# msp430g2230_breakout.net
KiCad netlist of a schematic drawn in EAGLE
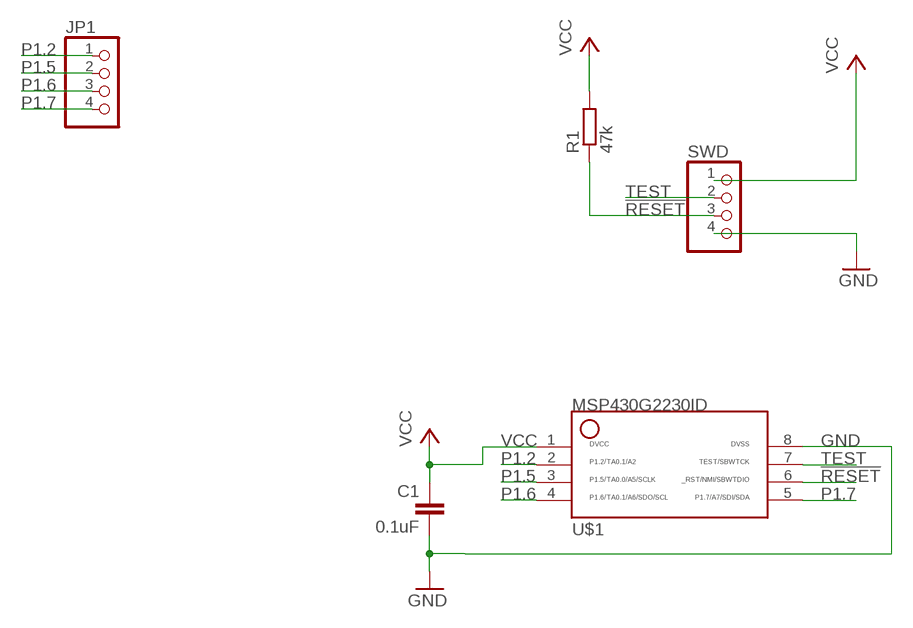
[diagram p0: schematic, sheet 1]

(export (version "E")
  (design (tool "Eeschema 10.0.6"))
  (components
    (comp (ref "C1")
      (value "0.1uF")
      (footprint "eagle-import:C0805")
      (libsource (lib "eagle-import") (part "C-EUC0805"))
    )
    (comp (ref "JP1")
      (value "PINHD-1X4")
      (footprint "eagle-import:1X04")
      (libsource (lib "eagle-import") (part "PINHD-1X4"))
    )
    (comp (ref "R1")
      (value "47k")
      (footprint "eagle-import:R0805")
      (libsource (lib "eagle-import") (part "R-EU_R0805"))
    )
    (comp (ref "SWD")
      (value "PINHD-1X4")
      (footprint "eagle-import:1X04")
      (libsource (lib "eagle-import") (part "PINHD-1X4"))
    )
    (comp (ref "U$1")
      (value "MSP430G2230ID")
      (footprint "eagle-import:SO08")
      (libsource (lib "eagle-import") (part "MSP430G2230ID"))
    )
  )
  (nets
    (net (code "1") (name "/P1.2") (class "Default")
      (node (ref "JP1") (pin "1") (pinfunction "1_1") (pintype "passive"))
      (node (ref "U$1") (pin "2") (pinfunction "2_2") (pintype "bidirectional"))
    )
    (net (code "2") (name "/P1.5") (class "Default")
      (node (ref "JP1") (pin "2") (pinfunction "2_2") (pintype "passive"))
      (node (ref "U$1") (pin "3") (pinfunction "3_3") (pintype "bidirectional"))
    )
    (net (code "3") (name "/P1.6") (class "Default")
      (node (ref "JP1") (pin "3") (pinfunction "3_3") (pintype "passive"))
      (node (ref "U$1") (pin "4") (pinfunction "4_4") (pintype "bidirectional"))
    )
    (net (code "4") (name "/P1.7") (class "Default")
      (node (ref "JP1") (pin "4") (pinfunction "4_4") (pintype "passive"))
      (node (ref "U$1") (pin "5") (pinfunction "5_5") (pintype "bidirectional"))
    )
    (net (code "5") (name "/TEST") (class "Default")
      (node (ref "SWD") (pin "2") (pinfunction "2_2") (pintype "passive"))
      (node (ref "U$1") (pin "7") (pinfunction "7_7") (pintype "bidirectional"))
    )
    (net (code "6") (name "/~{RESET}") (class "Default")
      (node (ref "R1") (pin "1") (pinfunction "1_1") (pintype "passive"))
      (node (ref "SWD") (pin "3") (pinfunction "3_3") (pintype "passive"))
      (node (ref "U$1") (pin "6") (pinfunction "6_6") (pintype "bidirectional"))
    )
    (net (code "7") (name "GND") (class "Default")
      (node (ref "C1") (pin "2") (pinfunction "2_2") (pintype "passive"))
      (node (ref "SWD") (pin "4") (pinfunction "4_4") (pintype "passive"))
      (node (ref "U$1") (pin "8") (pinfunction "8_8") (pintype "power_in"))
    )
    (net (code "8") (name "VCC") (class "Default")
      (node (ref "C1") (pin "1") (pinfunction "1_1") (pintype "passive"))
      (node (ref "R1") (pin "2") (pinfunction "2_2") (pintype "passive"))
      (node (ref "SWD") (pin "1") (pinfunction "1_1") (pintype "passive"))
      (node (ref "U$1") (pin "1") (pinfunction "1_1") (pintype "power_in"))
    )
  )
)
